# schematic.net
KiCad netlist of a schematic drawn in Altium Designer
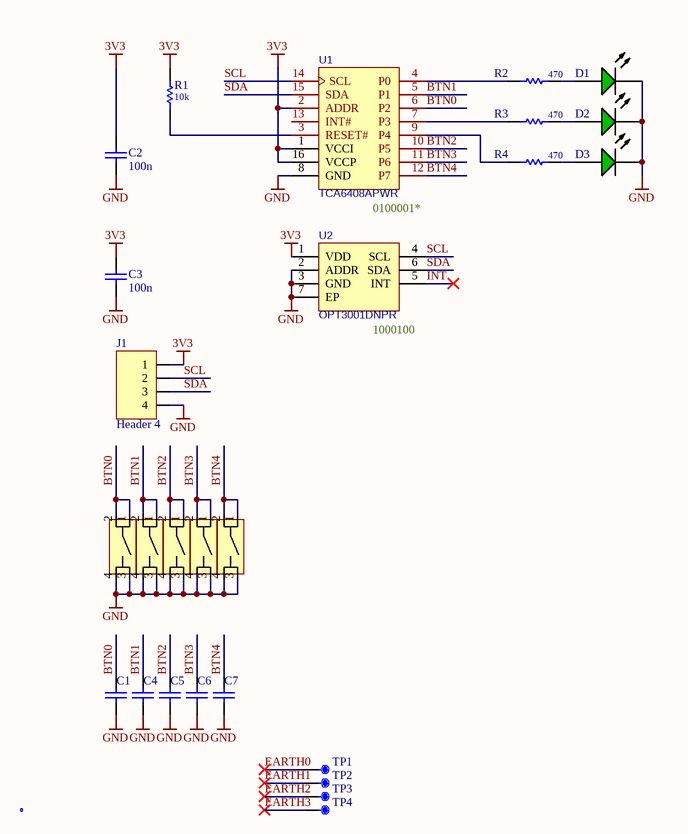
[diagram p0: schematic.SchDoc]

(export (version "E")
  (design (tool "Eeschema 10.0.6"))
  (components
    (comp (ref "C1")
      (value "100n")
      (footprint "C0402")
      (libsource (lib "Miscellaneous Devices") (part "Cap"))
    )
    (comp (ref "C2")
      (value "100n")
      (footprint "C0402")
      (libsource (lib "Miscellaneous Devices") (part "Cap"))
    )
    (comp (ref "C3")
      (value "100n")
      (footprint "C0402")
      (libsource (lib "Miscellaneous Devices") (part "Cap"))
    )
    (comp (ref "C4")
      (value "100n")
      (footprint "C0402")
      (libsource (lib "Miscellaneous Devices") (part "Cap"))
    )
    (comp (ref "C5")
      (value "100n")
      (footprint "C0402")
      (libsource (lib "Miscellaneous Devices") (part "Cap"))
    )
    (comp (ref "C6")
      (value "100n")
      (footprint "C0402")
      (libsource (lib "Miscellaneous Devices") (part "Cap"))
    )
    (comp (ref "C7")
      (value "100n")
      (footprint "C0402")
      (libsource (lib "Miscellaneous Devices") (part "Cap"))
    )
    (comp (ref "D1")
      (value "GRN")
      (footprint "LED-0603-GRN")
      (description "LED 0603 GRN")
      (fields (field (name "LCSC PART NUMBER") "C434420"))
      (libsource (lib "Miscellaneous Devices") (part "LED-0603-GREEN"))
    )
    (comp (ref "D2")
      (value "GRN")
      (footprint "LED-0603-GRN")
      (description "LED 0603 GRN")
      (fields (field (name "LCSC PART NUMBER") "C434420"))
      (libsource (lib "Miscellaneous Devices") (part "LED-0603-GREEN"))
    )
    (comp (ref "D3")
      (value "GRN")
      (footprint "LED-0603-GRN")
      (description "LED 0603 GRN")
      (fields (field (name "LCSC PART NUMBER") "C434420"))
      (libsource (lib "Miscellaneous Devices") (part "LED-0603-GREEN"))
    )
    (comp (ref "J1")
      (value "Header 4")
      (footprint "HDR-1x4-P1.25")
      (libsource (lib "Schlib1") (part "Header 3"))
    )
    (comp (ref "LOGO1") (value "LOGO") (footprint "LOGO") (libsource (lib "Schlib1") (part "LOGO")))
    (comp (ref "R1") (value "10k") (footprint "R0402") (libsource (lib "RR_Passive") (part "RES")))
    (comp (ref "R2")
      (value "470")
      (footprint "R0402")
      (fields (field (name "LCSC PART NUMBER") "C112291"))
      (libsource (lib "Miscellaneous Devices") (part "RES"))
    )
    (comp (ref "R3")
      (value "470")
      (footprint "R0402")
      (fields (field (name "LCSC PART NUMBER") "C112291"))
      (libsource (lib "Miscellaneous Devices") (part "RES"))
    )
    (comp (ref "R4")
      (value "470")
      (footprint "R0402")
      (fields (field (name "LCSC PART NUMBER") "C112291"))
      (libsource (lib "Miscellaneous Devices") (part "RES"))
    )
    (comp (ref "SW1")
      (value "TS-1187A-B-A-B")
      (footprint "SW-SMD_4P-L5.1-W5.1-P3.70-LS6.5-TL-2")
      (fields (field (name "LCSC PART NUMBER") "C318884"))
      (libsource (lib "Miscellaneous Devices") (part "Component_1"))
    )
    (comp (ref "SW2")
      (value "TS-1187A-B-A-B")
      (footprint "SW-SMD_4P-L5.1-W5.1-P3.70-LS6.5-TL-2")
      (fields (field (name "LCSC PART NUMBER") "C318884"))
      (libsource (lib "Miscellaneous Devices") (part "Component_1"))
    )
    (comp (ref "SW3")
      (value "TS-1187A-B-A-B")
      (footprint "SW-SMD_4P-L5.1-W5.1-P3.70-LS6.5-TL-2")
      (fields (field (name "LCSC PART NUMBER") "C318884"))
      (libsource (lib "Miscellaneous Devices") (part "Component_1"))
    )
    (comp (ref "SW4")
      (value "TS-1187A-B-A-B")
      (footprint "SW-SMD_4P-L5.1-W5.1-P3.70-LS6.5-TL-2")
      (fields (field (name "LCSC PART NUMBER") "C318884"))
      (libsource (lib "Miscellaneous Devices") (part "Component_1"))
    )
    (comp (ref "SW5")
      (value "TS-1187A-B-A-B")
      (footprint "SW-SMD_4P-L5.1-W5.1-P3.70-LS6.5-TL-2")
      (fields (field (name "LCSC PART NUMBER") "C318884"))
      (libsource (lib "Miscellaneous Devices") (part "Component_1"))
    )
    (comp (ref "TP1")
      (value "~")
      (footprint "TP30_SMD")
      (libsource (lib "Miscellaneous Devices") (part "TP_Dup1"))
    )
    (comp (ref "TP2")
      (value "~")
      (footprint "TP30_SMD")
      (libsource (lib "Miscellaneous Devices") (part "TP_Dup1"))
    )
    (comp (ref "TP3")
      (value "~")
      (footprint "TP30_SMD")
      (libsource (lib "Miscellaneous Devices") (part "TP_Dup1"))
    )
    (comp (ref "TP4")
      (value "~")
      (footprint "TP30_SMD")
      (libsource (lib "Miscellaneous Devices") (part "TP_Dup1"))
    )
    (comp (ref "U1")
      (value "TCA6408APWR")
      (footprint "TSSOP-16")
      (fields (field (name "LCSC PART NUMBER") "C206177"))
      (libsource (lib "Schlib1") (part "TCA6408APWR"))
    )
    (comp (ref "U2")
      (value "OPT3001DNPR")
      (footprint "USON6_L2.1-W2.1-P0.65-BL-EP")
      (fields (field (name "LCSC PART NUMBER") "C90462"))
      (libsource (lib "Schlib1") (part "OPT3001DNPR"))
    )
  )
  (nets
    (net (code "1") (name "/BTN0") (class "Default")
      (node (ref "C1") (pin "2") (pinfunction "2_2") (pintype "passive"))
      (node (ref "SW1") (pin "1") (pinfunction "1_1") (pintype "passive"))
      (node (ref "SW1") (pin "2") (pinfunction "2_2") (pintype "passive"))
      (node (ref "U1") (pin "6") (pinfunction "P2_6") (pintype "passive"))
    )
    (net (code "2") (name "/BTN1") (class "Default")
      (node (ref "C4") (pin "2") (pinfunction "2_2") (pintype "passive"))
      (node (ref "SW2") (pin "1") (pinfunction "1_1") (pintype "passive"))
      (node (ref "SW2") (pin "2") (pinfunction "2_2") (pintype "passive"))
      (node (ref "U1") (pin "5") (pinfunction "P1_5") (pintype "passive"))
    )
    (net (code "3") (name "/BTN2") (class "Default")
      (node (ref "C5") (pin "2") (pinfunction "2_2") (pintype "passive"))
      (node (ref "SW3") (pin "1") (pinfunction "1_1") (pintype "passive"))
      (node (ref "SW3") (pin "2") (pinfunction "2_2") (pintype "passive"))
      (node (ref "U1") (pin "10") (pinfunction "P5_10") (pintype "passive"))
    )
    (net (code "4") (name "/BTN3") (class "Default")
      (node (ref "C6") (pin "2") (pinfunction "2_2") (pintype "passive"))
      (node (ref "SW4") (pin "1") (pinfunction "1_1") (pintype "passive"))
      (node (ref "SW4") (pin "2") (pinfunction "2_2") (pintype "passive"))
      (node (ref "U1") (pin "11") (pinfunction "P6_11") (pintype "passive"))
    )
    (net (code "5") (name "/BTN4") (class "Default")
      (node (ref "C7") (pin "2") (pinfunction "2_2") (pintype "passive"))
      (node (ref "SW5") (pin "1") (pinfunction "1_1") (pintype "passive"))
      (node (ref "SW5") (pin "2") (pinfunction "2_2") (pintype "passive"))
      (node (ref "U1") (pin "12") (pinfunction "P7_12") (pintype "passive"))
    )
    (net (code "6") (name "/EARTH0") (class "Default")
      (node (ref "TP1") (pin "1") (pinfunction "1_1") (pintype "passive+no_connect"))
    )
    (net (code "7") (name "/EARTH1") (class "Default")
      (node (ref "TP2") (pin "1") (pinfunction "1_1") (pintype "passive+no_connect"))
    )
    (net (code "8") (name "/EARTH2") (class "Default")
      (node (ref "TP3") (pin "1") (pinfunction "1_1") (pintype "passive+no_connect"))
    )
    (net (code "9") (name "/EARTH3") (class "Default")
      (node (ref "TP4") (pin "1") (pinfunction "1_1") (pintype "passive+no_connect"))
    )
    (net (code "10") (name "/INT") (class "Default")
      (node (ref "U2") (pin "5") (pinfunction "INT_5") (pintype "passive+no_connect"))
    )
    (net (code "11") (name "/SCL") (class "Default")
      (node (ref "J1") (pin "2") (pinfunction "2_2") (pintype "passive"))
      (node (ref "U1") (pin "14") (pinfunction "SCL_14") (pintype "passive"))
      (node (ref "U2") (pin "4") (pinfunction "SCL_4") (pintype "passive"))
    )
    (net (code "12") (name "/SDA") (class "Default")
      (node (ref "J1") (pin "3") (pinfunction "3_3") (pintype "passive"))
      (node (ref "U1") (pin "15") (pinfunction "SDA_15") (pintype "passive"))
      (node (ref "U2") (pin "6") (pinfunction "SDA_6") (pintype "passive"))
    )
    (net (code "13") (name "3V3") (class "Default")
      (node (ref "C2") (pin "2") (pinfunction "2_2") (pintype "passive"))
      (node (ref "C3") (pin "2") (pinfunction "2_2") (pintype "passive"))
      (node (ref "J1") (pin "1") (pinfunction "1_1") (pintype "passive"))
      (node (ref "R1") (pin "2") (pinfunction "2_2") (pintype "passive"))
      (node (ref "U1") (pin "1") (pinfunction "VCCI_1") (pintype "passive"))
      (node (ref "U1") (pin "16") (pinfunction "VCCP_16") (pintype "passive"))
      (node (ref "U1") (pin "2") (pinfunction "ADDR_2") (pintype "passive"))
      (node (ref "U2") (pin "1") (pinfunction "VDD_1") (pintype "passive"))
    )
    (net (code "14") (name "GND") (class "Default")
      (node (ref "C1") (pin "1") (pinfunction "1_1") (pintype "passive"))
      (node (ref "C2") (pin "1") (pinfunction "1_1") (pintype "passive"))
      (node (ref "C3") (pin "1") (pinfunction "1_1") (pintype "passive"))
      (node (ref "C4") (pin "1") (pinfunction "1_1") (pintype "passive"))
      (node (ref "C5") (pin "1") (pinfunction "1_1") (pintype "passive"))
      (node (ref "C6") (pin "1") (pinfunction "1_1") (pintype "passive"))
      (node (ref "C7") (pin "1") (pinfunction "1_1") (pintype "passive"))
      (node (ref "D1") (pin "2") (pinfunction "K_2") (pintype "passive"))
      (node (ref "D2") (pin "2") (pinfunction "K_2") (pintype "passive"))
      (node (ref "D3") (pin "2") (pinfunction "K_2") (pintype "passive"))
      (node (ref "J1") (pin "4") (pinfunction "4_4") (pintype "passive"))
      (node (ref "SW1") (pin "3") (pinfunction "3_3") (pintype "passive"))
      (node (ref "SW1") (pin "4") (pinfunction "4_4") (pintype "passive"))
      (node (ref "SW2") (pin "3") (pinfunction "3_3") (pintype "passive"))
      (node (ref "SW2") (pin "4") (pinfunction "4_4") (pintype "passive"))
      (node (ref "SW3") (pin "3") (pinfunction "3_3") (pintype "passive"))
      (node (ref "SW3") (pin "4") (pinfunction "4_4") (pintype "passive"))
      (node (ref "SW4") (pin "3") (pinfunction "3_3") (pintype "passive"))
      (node (ref "SW4") (pin "4") (pinfunction "4_4") (pintype "passive"))
      (node (ref "SW5") (pin "3") (pinfunction "3_3") (pintype "passive"))
      (node (ref "SW5") (pin "4") (pinfunction "4_4") (pintype "passive"))
      (node (ref "U1") (pin "8") (pinfunction "GND_8") (pintype "passive"))
      (node (ref "U2") (pin "2") (pinfunction "ADDR_2") (pintype "passive"))
      (node (ref "U2") (pin "3") (pinfunction "GND_3") (pintype "passive"))
      (node (ref "U2") (pin "7") (pinfunction "EP_7") (pintype "passive"))
    )
    (net (code "15") (name "Net-(D1-A)") (class "Default")
      (node (ref "D1") (pin "1") (pinfunction "A_1") (pintype "passive"))
      (node (ref "R2") (pin "2") (pinfunction "2_2") (pintype "passive"))
    )
    (net (code "16") (name "Net-(D2-A)") (class "Default")
      (node (ref "D2") (pin "1") (pinfunction "A_1") (pintype "passive"))
      (node (ref "R3") (pin "2") (pinfunction "2_2") (pintype "passive"))
    )
    (net (code "17") (name "Net-(D3-A)") (class "Default")
      (node (ref "D3") (pin "1") (pinfunction "A_1") (pintype "passive"))
      (node (ref "R4") (pin "2") (pinfunction "2_2") (pintype "passive"))
    )
    (net (code "18") (name "Net-(U1-P0)") (class "Default")
      (node (ref "R2") (pin "1") (pinfunction "1_1") (pintype "passive"))
      (node (ref "U1") (pin "4") (pinfunction "P0_4") (pintype "passive"))
    )
    (net (code "19") (name "Net-(U1-P3)") (class "Default")
      (node (ref "R3") (pin "1") (pinfunction "1_1") (pintype "passive"))
      (node (ref "U1") (pin "7") (pinfunction "P3_7") (pintype "passive"))
    )
    (net (code "20") (name "Net-(U1-P4)") (class "Default")
      (node (ref "R4") (pin "1") (pinfunction "1_1") (pintype "passive"))
      (node (ref "U1") (pin "9") (pinfunction "P4_9") (pintype "passive"))
    )
    (net (code "21") (name "Net-(U1-RESET#)") (class "Default")
      (node (ref "R1") (pin "1") (pinfunction "1_1") (pintype "passive"))
      (node (ref "U1") (pin "3") (pinfunction "RESET#_3") (pintype "passive"))
    )
    (net (code "22") (name "unconnected-(U1-INT#-Pad13)") (class "Default")
      (node (ref "U1") (pin "13") (pinfunction "INT#_13") (pintype "passive"))
    )
  )
)
